# ClockGenerator.net
KiCad netlist of a schematic drawn in Altium Designer
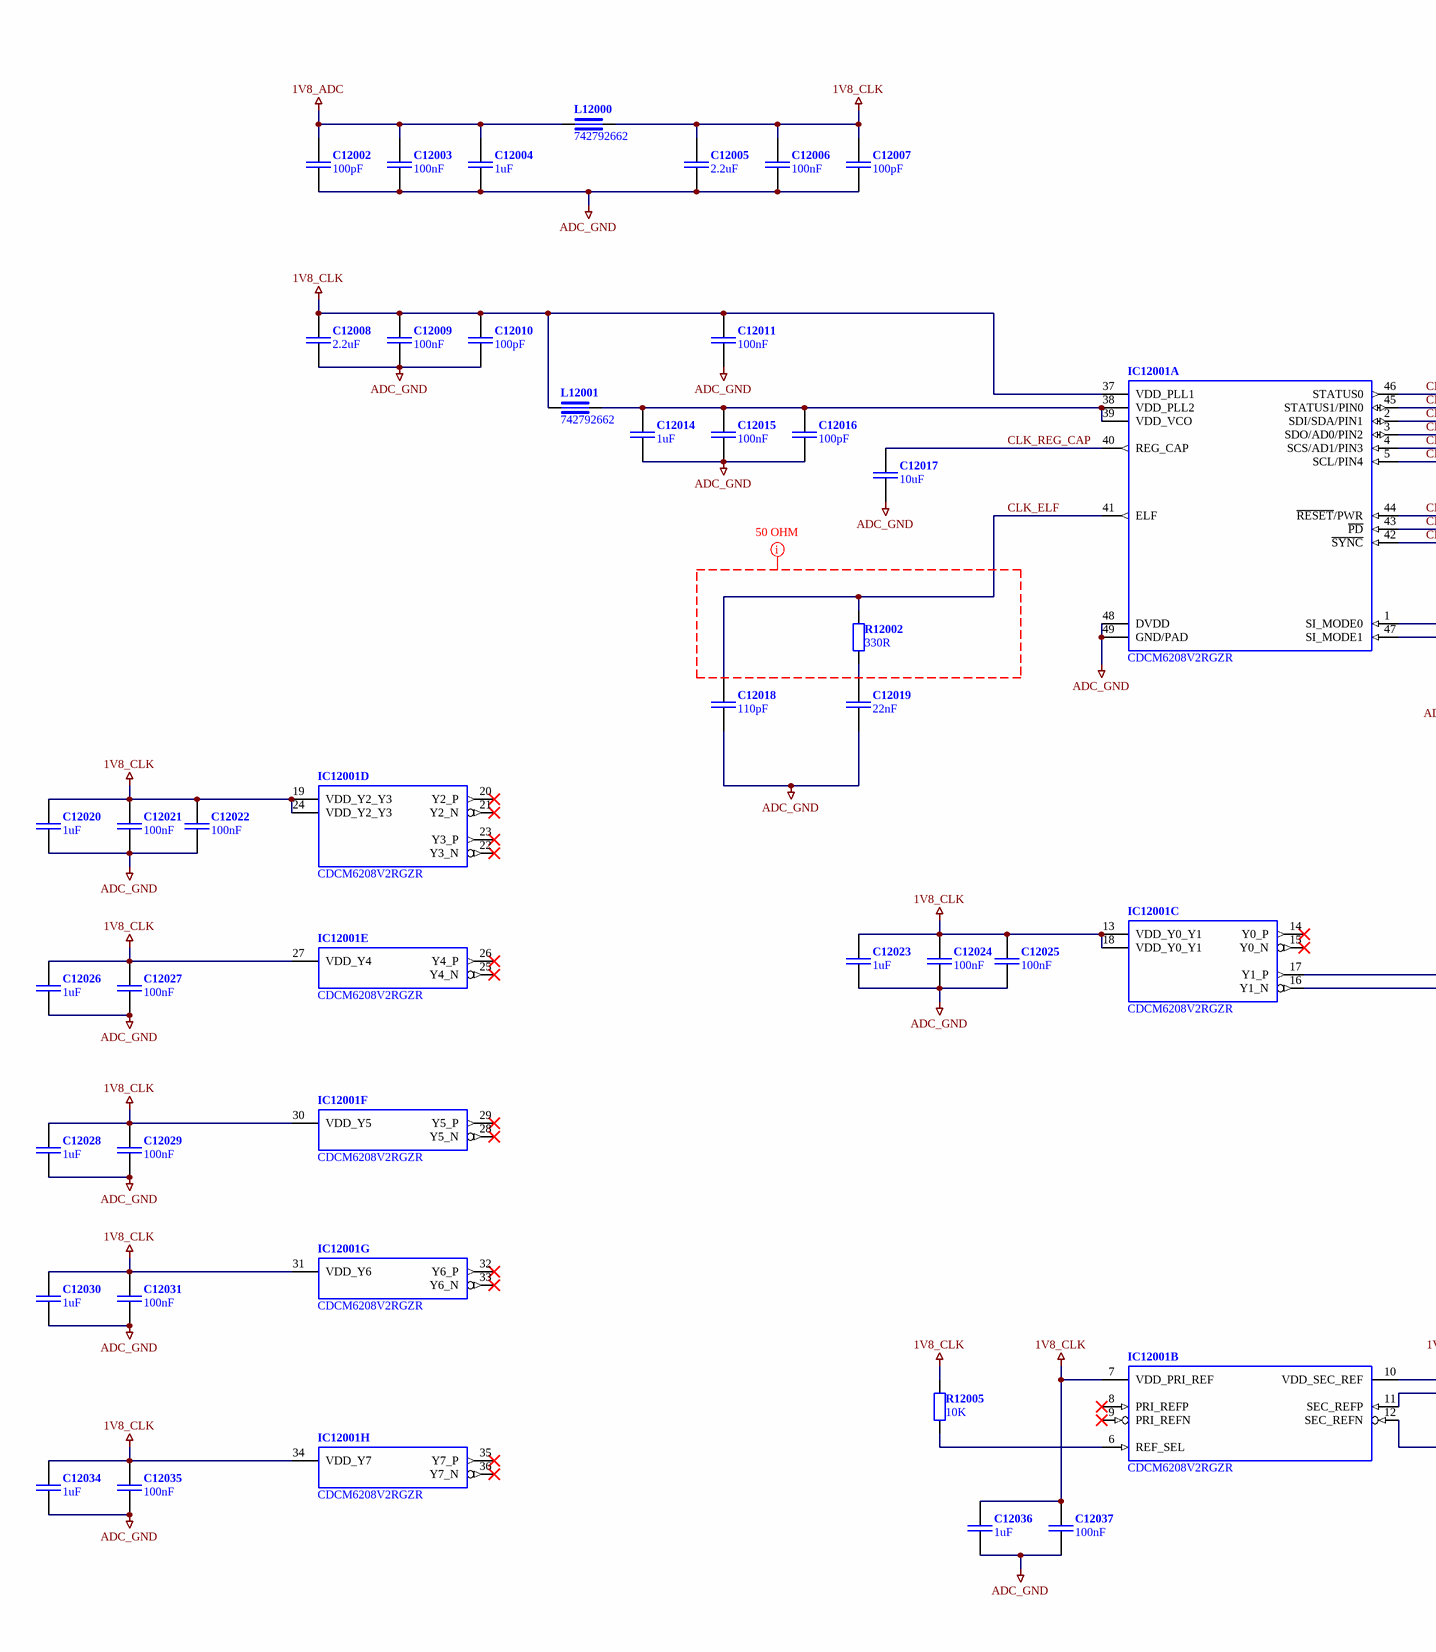
[diagram p0: ClockGenerator.SchDoc, left]
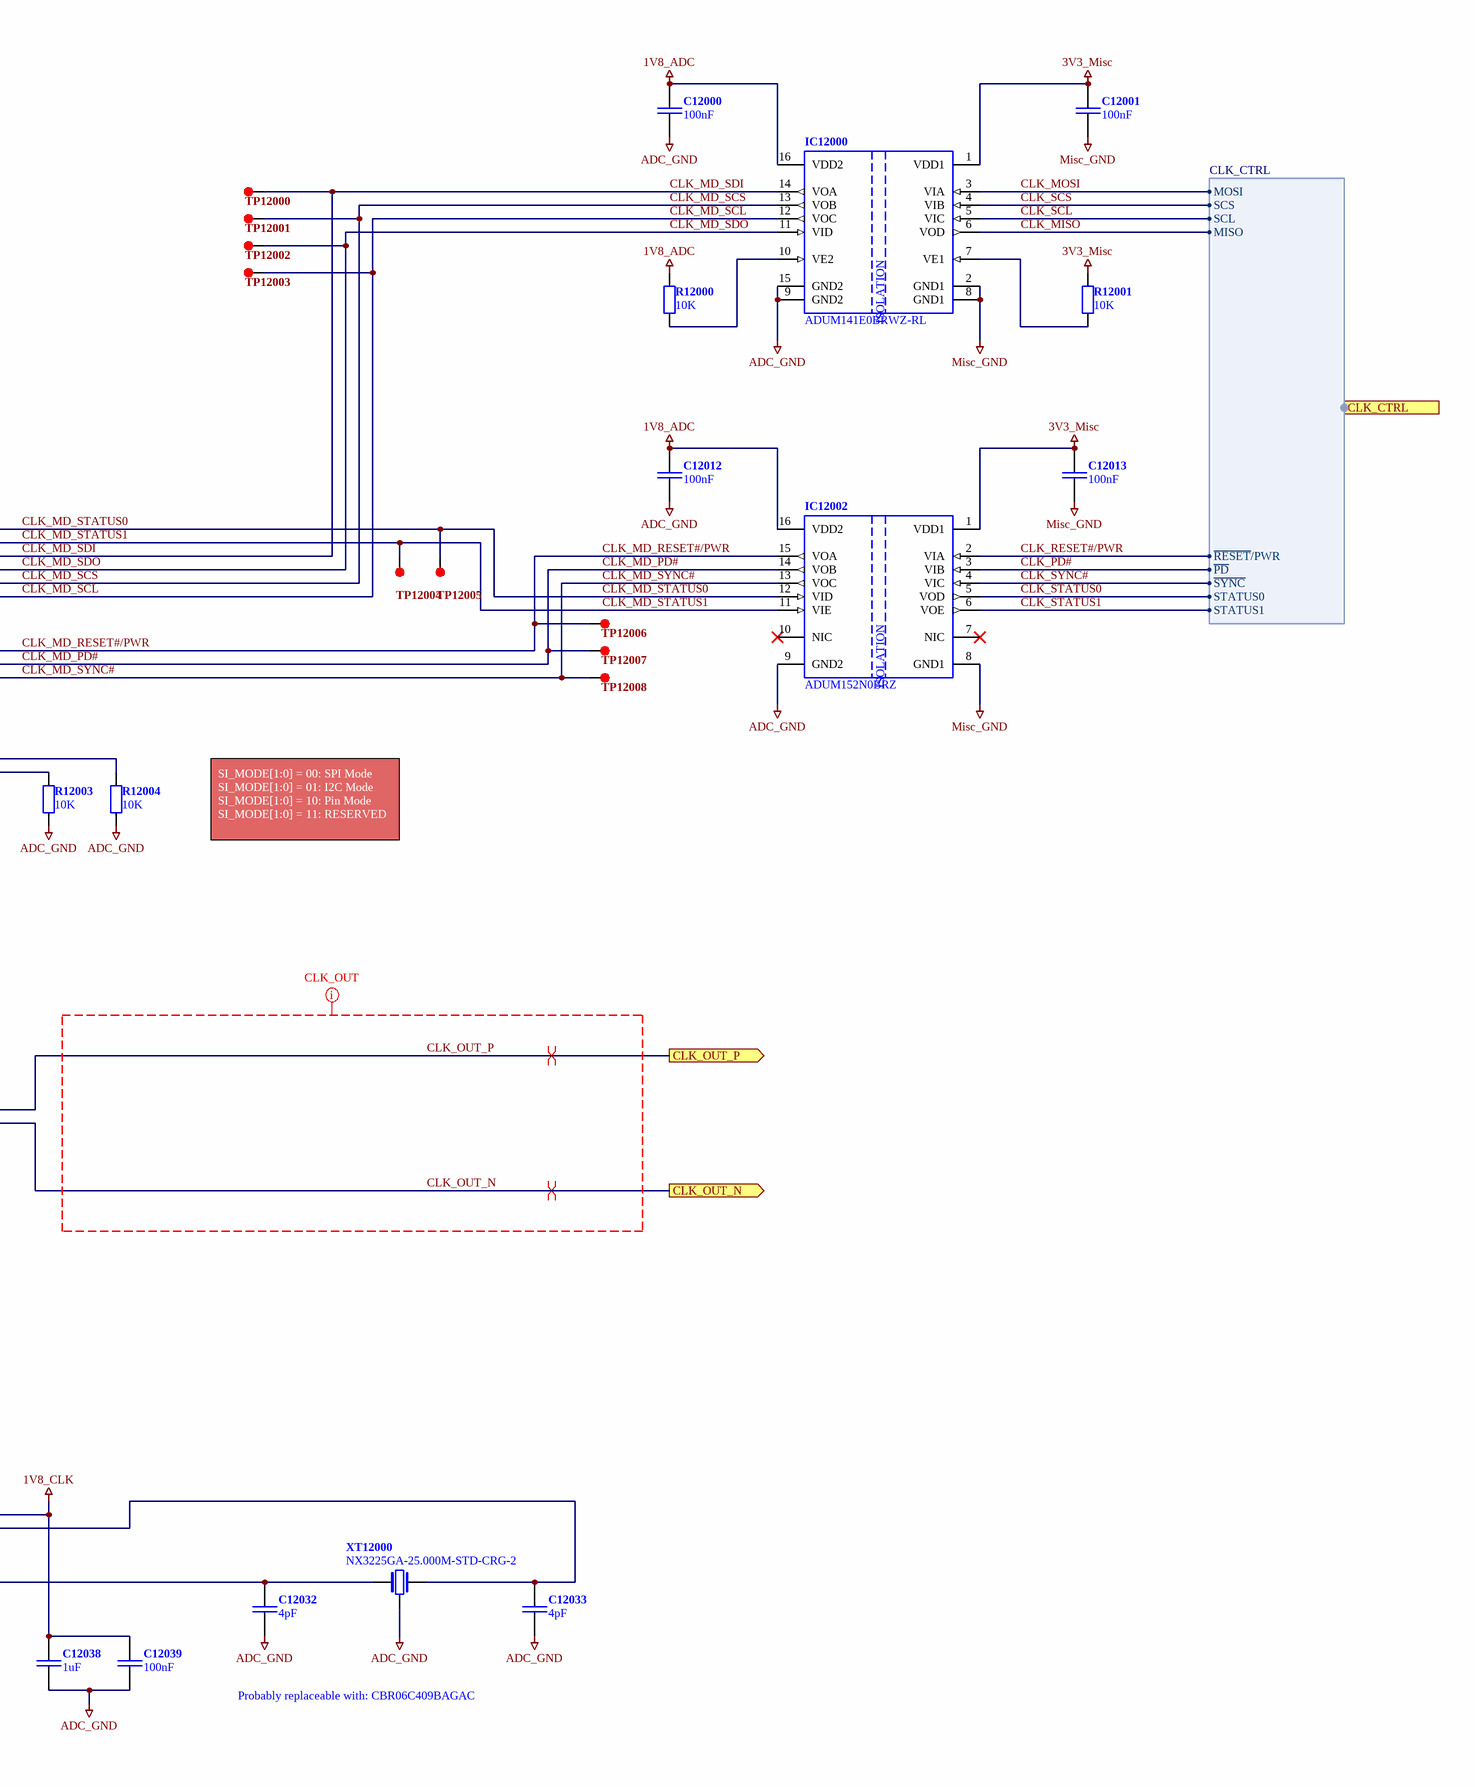
[diagram p1: ClockGenerator.SchDoc, right]

(export (version "E")
  (design (tool "Eeschema 10.0.6"))
  (components
    (comp (ref "C12000")
      (value "100nF")
      (footprint "PrometheusLib:C_0603_N [CAPC1608N IPC]")
      (libsource (lib "PrometheusLib") (part "C_GENERIC"))
    )
    (comp (ref "C12001")
      (value "100nF")
      (footprint "PrometheusLib:C_0603_N [CAPC1608N IPC]")
      (libsource (lib "PrometheusLib") (part "C_GENERIC"))
    )
    (comp (ref "C12002")
      (value "100pF")
      (footprint "PrometheusLib:C_0402_N [CAPC1005N IPC]")
      (libsource (lib "PrometheusLib") (part "C_GENERIC"))
    )
    (comp (ref "C12003")
      (value "100nF")
      (footprint "PrometheusLib:C_0603_N [CAPC1608N IPC]")
      (libsource (lib "PrometheusLib") (part "C_GENERIC"))
    )
    (comp (ref "C12004")
      (value "1uF")
      (footprint "PrometheusLib:C_0805_N [CAPC2013N IPC]")
      (libsource (lib "PrometheusLib") (part "C_GENERIC"))
    )
    (comp (ref "C12005")
      (value "2.2uF")
      (footprint "PrometheusLib:C_0805_N [CAPC2013N IPC]")
      (libsource (lib "PrometheusLib") (part "C_GENERIC"))
    )
    (comp (ref "C12006")
      (value "100nF")
      (footprint "PrometheusLib:C_0603_N [CAPC1608N IPC]")
      (libsource (lib "PrometheusLib") (part "C_GENERIC"))
    )
    (comp (ref "C12007")
      (value "100pF")
      (footprint "PrometheusLib:C_0402_N [CAPC1005N IPC]")
      (libsource (lib "PrometheusLib") (part "C_GENERIC"))
    )
    (comp (ref "C12008")
      (value "2.2uF")
      (footprint "PrometheusLib:C_0805_N [CAPC2013N IPC]")
      (libsource (lib "PrometheusLib") (part "C_GENERIC"))
    )
    (comp (ref "C12009")
      (value "100nF")
      (footprint "PrometheusLib:C_0603_N [CAPC1608N IPC]")
      (libsource (lib "PrometheusLib") (part "C_GENERIC"))
    )
    (comp (ref "C12010")
      (value "100pF")
      (footprint "PrometheusLib:C_0402_N [CAPC1005N IPC]")
      (libsource (lib "PrometheusLib") (part "C_GENERIC"))
    )
    (comp (ref "C12011")
      (value "100nF")
      (footprint "PrometheusLib:C_0603_N [CAPC1608N IPC]")
      (libsource (lib "PrometheusLib") (part "C_GENERIC"))
    )
    (comp (ref "C12012")
      (value "100nF")
      (footprint "PrometheusLib:C_0603_N [CAPC1608N IPC]")
      (libsource (lib "PrometheusLib") (part "C_GENERIC"))
    )
    (comp (ref "C12013")
      (value "100nF")
      (footprint "PrometheusLib:C_0603_N [CAPC1608N IPC]")
      (libsource (lib "PrometheusLib") (part "C_GENERIC"))
    )
    (comp (ref "C12014")
      (value "1uF")
      (footprint "PrometheusLib:C_0805_N [CAPC2013N IPC]")
      (libsource (lib "PrometheusLib") (part "C_GENERIC"))
    )
    (comp (ref "C12015")
      (value "100nF")
      (footprint "PrometheusLib:C_0603_N [CAPC1608N IPC]")
      (libsource (lib "PrometheusLib") (part "C_GENERIC"))
    )
    (comp (ref "C12016")
      (value "100pF")
      (footprint "PrometheusLib:C_0402_N [CAPC1005N IPC]")
      (libsource (lib "PrometheusLib") (part "C_GENERIC"))
    )
    (comp (ref "C12017")
      (value "10uF")
      (footprint "PrometheusLib:C_0805_N [CAPC2013N IPC]")
      (fields (field (name "PROMETHEUS_MANPARTNO") "GRM188R60J106KE47D"))
      (libsource (lib "PrometheusLib") (part "C_GENERIC"))
    )
    (comp (ref "C12018")
      (value "110pF")
      (footprint "PrometheusLib:C_0603_N [CAPC1608N IPC]")
      (libsource (lib "PrometheusLib") (part "C_GENERIC"))
    )
    (comp (ref "C12019")
      (value "22nF")
      (footprint "PrometheusLib:C_0603_N [CAPC1608N IPC]")
      (libsource (lib "PrometheusLib") (part "C_GENERIC"))
    )
    (comp (ref "C12020")
      (value "1uF")
      (footprint "PrometheusLib:C_0805_N [CAPC2013N IPC]")
      (libsource (lib "PrometheusLib") (part "C_GENERIC"))
    )
    (comp (ref "C12021")
      (value "100nF")
      (footprint "PrometheusLib:C_0603_N [CAPC1608N IPC]")
      (libsource (lib "PrometheusLib") (part "C_GENERIC"))
    )
    (comp (ref "C12022")
      (value "100nF")
      (footprint "PrometheusLib:C_0603_N [CAPC1608N IPC]")
      (libsource (lib "PrometheusLib") (part "C_GENERIC"))
    )
    (comp (ref "C12023")
      (value "1uF")
      (footprint "PrometheusLib:C_0805_N [CAPC2013N IPC]")
      (libsource (lib "PrometheusLib") (part "C_GENERIC"))
    )
    (comp (ref "C12024")
      (value "100nF")
      (footprint "PrometheusLib:C_0603_N [CAPC1608N IPC]")
      (libsource (lib "PrometheusLib") (part "C_GENERIC"))
    )
    (comp (ref "C12025")
      (value "100nF")
      (footprint "PrometheusLib:C_0603_N [CAPC1608N IPC]")
      (libsource (lib "PrometheusLib") (part "C_GENERIC"))
    )
    (comp (ref "C12026")
      (value "1uF")
      (footprint "PrometheusLib:C_0805_N [CAPC2013N IPC]")
      (libsource (lib "PrometheusLib") (part "C_GENERIC"))
    )
    (comp (ref "C12027")
      (value "100nF")
      (footprint "PrometheusLib:C_0603_N [CAPC1608N IPC]")
      (libsource (lib "PrometheusLib") (part "C_GENERIC"))
    )
    (comp (ref "C12028")
      (value "1uF")
      (footprint "PrometheusLib:C_0805_N [CAPC2013N IPC]")
      (libsource (lib "PrometheusLib") (part "C_GENERIC"))
    )
    (comp (ref "C12029")
      (value "100nF")
      (footprint "PrometheusLib:C_0603_N [CAPC1608N IPC]")
      (libsource (lib "PrometheusLib") (part "C_GENERIC"))
    )
    (comp (ref "C12030")
      (value "1uF")
      (footprint "PrometheusLib:C_0805_N [CAPC2013N IPC]")
      (libsource (lib "PrometheusLib") (part "C_GENERIC"))
    )
    (comp (ref "C12031")
      (value "100nF")
      (footprint "PrometheusLib:C_0603_N [CAPC1608N IPC]")
      (libsource (lib "PrometheusLib") (part "C_GENERIC"))
    )
    (comp (ref "C12032")
      (value "4pF")
      (footprint "PrometheusLib:C_0603_N [CAPC1608N IPC]")
      (description "+- 0.05 pF")
      (fields (field (name "PROMETHEUS_MANPARTNO") "CBR06C409A1GAC"))
      (libsource (lib "PrometheusLib") (part "C_GENERIC"))
    )
    (comp (ref "C12033")
      (value "4pF")
      (footprint "PrometheusLib:C_0603_N [CAPC1608N IPC]")
      (description "+- 0.05 pF")
      (fields (field (name "PROMETHEUS_MANPARTNO") "CBR06C409A1GAC"))
      (libsource (lib "PrometheusLib") (part "C_GENERIC"))
    )
    (comp (ref "C12034")
      (value "1uF")
      (footprint "PrometheusLib:C_0805_N [CAPC2013N IPC]")
      (libsource (lib "PrometheusLib") (part "C_GENERIC"))
    )
    (comp (ref "C12035")
      (value "100nF")
      (footprint "PrometheusLib:C_0603_N [CAPC1608N IPC]")
      (libsource (lib "PrometheusLib") (part "C_GENERIC"))
    )
    (comp (ref "C12036")
      (value "1uF")
      (footprint "PrometheusLib:C_0805_N [CAPC2013N IPC]")
      (libsource (lib "PrometheusLib") (part "C_GENERIC"))
    )
    (comp (ref "C12037")
      (value "100nF")
      (footprint "PrometheusLib:C_0603_N [CAPC1608N IPC]")
      (libsource (lib "PrometheusLib") (part "C_GENERIC"))
    )
    (comp (ref "C12038")
      (value "1uF")
      (footprint "PrometheusLib:C_0805_N [CAPC2013N IPC]")
      (libsource (lib "PrometheusLib") (part "C_GENERIC"))
    )
    (comp (ref "C12039")
      (value "100nF")
      (footprint "PrometheusLib:C_0603_N [CAPC1608N IPC]")
      (libsource (lib "PrometheusLib") (part "C_GENERIC"))
    )
    (comp (ref "IC12000")
      (value "ADUM141E0BRWZ-RL")
      (footprint "SOIC127P1030X265-16N IPC")
      (description "3/1 digital isolator\r\n1.8 V to 5 V Level translation")
      (libsource (lib "PrometheusLib") (part "IC_ADUM141E0BRWZ-RL"))
    )
    (comp (ref "IC12001")
      (value "CDCM6208V2RGZR")
      (footprint "QFN50P700X700X100_HS-49N IPC")
      (description "2:8 Clock Generator, Jitter Cleaner with fractional dividers")
      (libsource (lib "PrometheusLib") (part "IC_CDCM6208V2"))
    )
    (comp (ref "IC12002")
      (value "ADUM152N0BRZ")
      (footprint "SOIC127P600X175-16N IPC")
      (description "3/2 digital isolator\r\n1.8 V to 5 V Level translation")
      (libsource (lib "PrometheusLib") (part "IC_ADUM152N0BRZ"))
    )
    (comp (ref "L12000")
      (value "742792662")
      (footprint "PrometheusLib:L_0603_N [INDC1608N IPC]")
      (libsource (lib "PrometheusLib") (part "FB_GENERIC"))
    )
    (comp (ref "L12001")
      (value "742792662")
      (footprint "PrometheusLib:L_0603_N [INDC1608N IPC]")
      (libsource (lib "PrometheusLib") (part "FB_GENERIC"))
    )
    (comp (ref "R12000")
      (value "10K")
      (footprint "PrometheusLib:R_0603_N [RESC1608N IPC]")
      (libsource (lib "PrometheusLib") (part "R_GENERIC_DIN"))
    )
    (comp (ref "R12001")
      (value "10K")
      (footprint "PrometheusLib:R_0603_N [RESC1608N IPC]")
      (libsource (lib "") (part "R_GENERIC_DIN_1"))
    )
    (comp (ref "R12002")
      (value "330R")
      (footprint "PrometheusLib:R_0603_N [RESC1608N IPC]")
      (fields (field (name "PROMETHEUS_MANPARTNO") "ERJ-3EKF3300V"))
      (libsource (lib "PrometheusLib") (part "R_GENERIC_DIN"))
    )
    (comp (ref "R12003")
      (value "10K")
      (footprint "PrometheusLib:R_0603_N [RESC1608N IPC]")
      (libsource (lib "PrometheusLib") (part "R_GENERIC_DIN"))
    )
    (comp (ref "R12004")
      (value "10K")
      (footprint "PrometheusLib:R_0603_N [RESC1608N IPC]")
      (libsource (lib "PrometheusLib") (part "R_GENERIC_DIN"))
    )
    (comp (ref "R12005")
      (value "10K")
      (footprint "PrometheusLib:R_0603_N [RESC1608N IPC]")
      (libsource (lib "PrometheusLib") (part "R_GENERIC_DIN"))
    )
    (comp (ref "TP12000")
      (value "TP_GENERIC")
      (footprint "PrometheusLib:TP_0.8_P100T")
      (description "Needle Test Point")
      (libsource (lib "PrometheusLib") (part "TP_GENERIC"))
    )
    (comp (ref "TP12001")
      (value "TP_GENERIC")
      (footprint "PrometheusLib:TP_0.8_P100T")
      (description "Needle Test Point")
      (libsource (lib "PrometheusLib") (part "TP_GENERIC"))
    )
    (comp (ref "TP12002")
      (value "TP_GENERIC")
      (footprint "PrometheusLib:TP_0.8_P100T")
      (description "Needle Test Point")
      (libsource (lib "PrometheusLib") (part "TP_GENERIC"))
    )
    (comp (ref "TP12003")
      (value "TP_GENERIC")
      (footprint "PrometheusLib:TP_0.8_P100T")
      (description "Needle Test Point")
      (libsource (lib "PrometheusLib") (part "TP_GENERIC"))
    )
    (comp (ref "TP12004")
      (value "TP_GENERIC")
      (footprint "PrometheusLib:TP_0.8_P100T")
      (description "Needle Test Point")
      (libsource (lib "PrometheusLib") (part "TP_GENERIC"))
    )
    (comp (ref "TP12005")
      (value "TP_GENERIC")
      (footprint "PrometheusLib:TP_0.8_P100T")
      (description "Needle Test Point")
      (libsource (lib "PrometheusLib") (part "TP_GENERIC"))
    )
    (comp (ref "TP12006")
      (value "TP_GENERIC")
      (footprint "PrometheusLib:TP_0.8_P100T")
      (description "Needle Test Point")
      (libsource (lib "PrometheusLib") (part "TP_GENERIC"))
    )
    (comp (ref "TP12007")
      (value "TP_GENERIC")
      (footprint "PrometheusLib:TP_0.8_P100T")
      (description "Needle Test Point")
      (libsource (lib "PrometheusLib") (part "TP_GENERIC"))
    )
    (comp (ref "TP12008")
      (value "TP_GENERIC")
      (footprint "PrometheusLib:TP_0.8_P100T")
      (description "Needle Test Point")
      (libsource (lib "PrometheusLib") (part "TP_GENERIC"))
    )
    (comp (ref "XT12000")
      (value "NX3225GA-25.000M-STD-CRG-2")
      (footprint "PrometheusLib:XT_SMD_320x250_H100_4PIN")
      (description "25 MHz\r\n8 pF")
      (libsource (lib "PrometheusLib") (part "XT_NX3225GA-25.000M-STD-CRG-2"))
    )
  )
  (nets
    (net (code "2") (name "/CLK_ELF") (class "Default")
      (node (ref "C12018") (pin "2") (pintype "passive"))
      (node (ref "IC12001") (pin "41") (pinfunction "ELF_41") (pintype "output"))
      (node (ref "R12002") (pin "2") (pinfunction "2_2") (pintype "passive"))
    )
    (net (code "3") (name "/CLK_MD_PD#") (class "Default")
      (node (ref "IC12001") (pin "43") (pinfunction "~{PD}_43") (pintype "input"))
      (node (ref "IC12002") (pin "14") (pinfunction "VOB_14") (pintype "output"))
      (node (ref "TP12007") (pin "1") (pinfunction "1_1") (pintype "passive"))
    )
    (net (code "4") (name "/CLK_MD_RESET#{slash}PWR") (class "Default")
      (node (ref "IC12001") (pin "44") (pinfunction "~{RESET}/PWR_44") (pintype "input"))
      (node (ref "IC12002") (pin "15") (pinfunction "VOA_15") (pintype "output"))
      (node (ref "TP12006") (pin "1") (pinfunction "1_1") (pintype "passive"))
    )
    (net (code "5") (name "/CLK_MD_SCL") (class "Default")
      (node (ref "IC12000") (pin "12") (pinfunction "VOC_12") (pintype "output"))
      (node (ref "IC12001") (pin "5") (pinfunction "SCL/PIN4_5") (pintype "input"))
      (node (ref "TP12003") (pin "1") (pinfunction "1_1") (pintype "passive"))
    )
    (net (code "6") (name "/CLK_MD_SCS") (class "Default")
      (node (ref "IC12000") (pin "13") (pinfunction "VOB_13") (pintype "output"))
      (node (ref "IC12001") (pin "4") (pinfunction "SCS/AD1/PIN3_4") (pintype "input"))
      (node (ref "TP12001") (pin "1") (pinfunction "1_1") (pintype "passive"))
    )
    (net (code "7") (name "/CLK_MD_SDI") (class "Default")
      (node (ref "IC12000") (pin "14") (pinfunction "VOA_14") (pintype "output"))
      (node (ref "IC12001") (pin "2") (pinfunction "SDI/SDA/PIN1_2") (pintype "bidirectional"))
      (node (ref "TP12000") (pin "1") (pinfunction "1_1") (pintype "passive"))
    )
    (net (code "8") (name "/CLK_MD_SDO") (class "Default")
      (node (ref "IC12000") (pin "11") (pinfunction "VID_11") (pintype "input"))
      (node (ref "IC12001") (pin "3") (pinfunction "SDO/AD0/PIN2_3") (pintype "bidirectional"))
      (node (ref "TP12002") (pin "1") (pinfunction "1_1") (pintype "passive"))
    )
    (net (code "9") (name "/CLK_MD_STATUS0") (class "Default")
      (node (ref "IC12001") (pin "46") (pinfunction "STATUS0_46") (pintype "output"))
      (node (ref "IC12002") (pin "12") (pinfunction "VID_12") (pintype "input"))
      (node (ref "TP12005") (pin "1") (pinfunction "1_1") (pintype "passive"))
    )
    (net (code "10") (name "/CLK_MD_STATUS1") (class "Default")
      (node (ref "IC12001") (pin "45") (pinfunction "STATUS1/PIN0_45") (pintype "bidirectional"))
      (node (ref "IC12002") (pin "11") (pinfunction "VIE_11") (pintype "input"))
      (node (ref "TP12004") (pin "1") (pinfunction "1_1") (pintype "passive"))
    )
    (net (code "11") (name "/CLK_MD_SYNC#") (class "Default")
      (node (ref "IC12001") (pin "42") (pinfunction "~{SYNC}_42") (pintype "input"))
      (node (ref "IC12002") (pin "13") (pinfunction "VOC_13") (pintype "output"))
      (node (ref "TP12008") (pin "1") (pinfunction "1_1") (pintype "passive"))
    )
    (net (code "12") (name "/CLK_MISO") (class "Default")
      (node (ref "IC12000") (pin "6") (pinfunction "VOD_6") (pintype "output"))
    )
    (net (code "13") (name "/CLK_MOSI") (class "Default")
      (node (ref "IC12000") (pin "3") (pinfunction "VIA_3") (pintype "input"))
    )
    (net (code "14") (name "/CLK_OUT_N") (class "Default")
      (node (ref "IC12001") (pin "16") (pinfunction "Y1_N_16") (pintype "output"))
    )
    (net (code "15") (name "/CLK_OUT_P") (class "Default")
      (node (ref "IC12001") (pin "17") (pinfunction "Y1_P_17") (pintype "output"))
    )
    (net (code "16") (name "/CLK_PD#") (class "Default")
      (node (ref "IC12002") (pin "3") (pinfunction "VIB_3") (pintype "input"))
    )
    (net (code "17") (name "/CLK_REG_CAP") (class "Default")
      (node (ref "C12017") (pin "1") (pintype "passive"))
      (node (ref "IC12001") (pin "40") (pinfunction "REG_CAP_40") (pintype "output"))
    )
    (net (code "18") (name "/CLK_RESET#{slash}PWR") (class "Default")
      (node (ref "IC12002") (pin "2") (pinfunction "VIA_2") (pintype "input"))
    )
    (net (code "19") (name "/CLK_SCL") (class "Default")
      (node (ref "IC12000") (pin "5") (pinfunction "VIC_5") (pintype "input"))
    )
    (net (code "20") (name "/CLK_SCS") (class "Default")
      (node (ref "IC12000") (pin "4") (pinfunction "VIB_4") (pintype "input"))
    )
    (net (code "21") (name "/CLK_STATUS0") (class "Default")
      (node (ref "IC12002") (pin "5") (pinfunction "VOD_5") (pintype "output"))
    )
    (net (code "22") (name "/CLK_STATUS1") (class "Default")
      (node (ref "IC12002") (pin "6") (pinfunction "VOE_6") (pintype "output"))
    )
    (net (code "23") (name "/CLK_SYNC#") (class "Default")
      (node (ref "IC12002") (pin "4") (pinfunction "VIC_4") (pintype "input"))
    )
    (net (code "25") (name "1V8_ADC") (class "Default")
      (node (ref "C12000") (pin "1") (pintype "passive"))
      (node (ref "C12002") (pin "1") (pintype "passive"))
      (node (ref "C12003") (pin "1") (pintype "passive"))
      (node (ref "C12004") (pin "1") (pintype "passive"))
      (node (ref "C12012") (pin "1") (pintype "passive"))
      (node (ref "IC12000") (pin "16") (pinfunction "VDD2_16") (pintype "passive"))
      (node (ref "IC12002") (pin "16") (pinfunction "VDD2_16") (pintype "passive"))
      (node (ref "L12000") (pin "2") (pintype "passive"))
      (node (ref "R12000") (pin "2") (pinfunction "2_2") (pintype "passive"))
    )
    (net (code "26") (name "1V8_CLK") (class "Default")
      (node (ref "C12005") (pin "1") (pintype "passive"))
      (node (ref "C12006") (pin "1") (pintype "passive"))
      (node (ref "C12007") (pin "1") (pintype "passive"))
      (node (ref "C12008") (pin "1") (pintype "passive"))
      (node (ref "C12009") (pin "1") (pintype "passive"))
      (node (ref "C12010") (pin "1") (pintype "passive"))
      (node (ref "C12011") (pin "1") (pintype "passive"))
      (node (ref "C12020") (pin "1") (pintype "passive"))
      (node (ref "C12021") (pin "1") (pintype "passive"))
      (node (ref "C12022") (pin "1") (pintype "passive"))
      (node (ref "C12023") (pin "1") (pintype "passive"))
      (node (ref "C12024") (pin "1") (pintype "passive"))
      (node (ref "C12025") (pin "1") (pintype "passive"))
      (node (ref "C12026") (pin "1") (pintype "passive"))
      (node (ref "C12027") (pin "1") (pintype "passive"))
      (node (ref "C12028") (pin "1") (pintype "passive"))
      (node (ref "C12029") (pin "1") (pintype "passive"))
      (node (ref "C12030") (pin "1") (pintype "passive"))
      (node (ref "C12031") (pin "1") (pintype "passive"))
      (node (ref "C12034") (pin "1") (pintype "passive"))
      (node (ref "C12035") (pin "1") (pintype "passive"))
      (node (ref "C12036") (pin "1") (pintype "passive"))
      (node (ref "C12037") (pin "1") (pintype "passive"))
      (node (ref "C12038") (pin "1") (pintype "passive"))
      (node (ref "C12039") (pin "1") (pintype "passive"))
      (node (ref "IC12001") (pin "10") (pinfunction "VDD_SEC_REF_10") (pintype "passive"))
      (node (ref "IC12001") (pin "13") (pinfunction "VDD_Y0_Y1_13") (pintype "passive"))
      (node (ref "IC12001") (pin "18") (pinfunction "VDD_Y0_Y1_18") (pintype "passive"))
      (node (ref "IC12001") (pin "19") (pinfunction "VDD_Y2_Y3_19") (pintype "passive"))
      (node (ref "IC12001") (pin "24") (pinfunction "VDD_Y2_Y3_24") (pintype "passive"))
      (node (ref "IC12001") (pin "27") (pinfunction "VDD_Y4_27") (pintype "passive"))
      (node (ref "IC12001") (pin "30") (pinfunction "VDD_Y5_30") (pintype "passive"))
      (node (ref "IC12001") (pin "31") (pinfunction "VDD_Y6_31") (pintype "passive"))
      (node (ref "IC12001") (pin "34") (pinfunction "VDD_Y7_34") (pintype "passive"))
      (node (ref "IC12001") (pin "37") (pinfunction "VDD_PLL1_37") (pintype "passive"))
      (node (ref "IC12001") (pin "7") (pinfunction "VDD_PRI_REF_7") (pintype "passive"))
      (node (ref "L12000") (pin "1") (pintype "passive"))
      (node (ref "L12001") (pin "2") (pintype "passive"))
      (node (ref "R12005") (pin "2") (pinfunction "2_2") (pintype "passive"))
    )
    (net (code "27") (name "3V3_Misc") (class "Default")
      (node (ref "C12001") (pin "1") (pintype "passive"))
      (node (ref "C12013") (pin "1") (pintype "passive"))
      (node (ref "IC12000") (pin "1") (pinfunction "VDD1_1") (pintype "passive"))
      (node (ref "IC12002") (pin "1") (pinfunction "VDD1_1") (pintype "passive"))
      (node (ref "R12001") (pin "2") (pinfunction "2_2") (pintype "passive"))
    )
    (net (code "28") (name "ADC_GND") (class "Default")
      (node (ref "C12000") (pin "2") (pintype "passive"))
      (node (ref "C12002") (pin "2") (pintype "passive"))
      (node (ref "C12003") (pin "2") (pintype "passive"))
      (node (ref "C12004") (pin "2") (pintype "passive"))
      (node (ref "C12005") (pin "2") (pintype "passive"))
      (node (ref "C12006") (pin "2") (pintype "passive"))
      (node (ref "C12007") (pin "2") (pintype "passive"))
      (node (ref "C12008") (pin "2") (pintype "passive"))
      (node (ref "C12009") (pin "2") (pintype "passive"))
      (node (ref "C12010") (pin "2") (pintype "passive"))
      (node (ref "C12011") (pin "2") (pintype "passive"))
      (node (ref "C12012") (pin "2") (pintype "passive"))
      (node (ref "C12014") (pin "2") (pintype "passive"))
      (node (ref "C12015") (pin "2") (pintype "passive"))
      (node (ref "C12016") (pin "2") (pintype "passive"))
      (node (ref "C12017") (pin "2") (pintype "passive"))
      (node (ref "C12018") (pin "1") (pintype "passive"))
      (node (ref "C12019") (pin "1") (pintype "passive"))
      (node (ref "C12020") (pin "2") (pintype "passive"))
      (node (ref "C12021") (pin "2") (pintype "passive"))
      (node (ref "C12022") (pin "2") (pintype "passive"))
      (node (ref "C12023") (pin "2") (pintype "passive"))
      (node (ref "C12024") (pin "2") (pintype "passive"))
      (node (ref "C12025") (pin "2") (pintype "passive"))
      (node (ref "C12026") (pin "2") (pintype "passive"))
      (node (ref "C12027") (pin "2") (pintype "passive"))
      (node (ref "C12028") (pin "2") (pintype "passive"))
      (node (ref "C12029") (pin "2") (pintype "passive"))
      (node (ref "C12030") (pin "2") (pintype "passive"))
      (node (ref "C12031") (pin "2") (pintype "passive"))
      (node (ref "C12032") (pin "2") (pintype "passive"))
      (node (ref "C12033") (pin "2") (pintype "passive"))
      (node (ref "C12034") (pin "2") (pintype "passive"))
      (node (ref "C12035") (pin "2") (pintype "passive"))
      (node (ref "C12036") (pin "2") (pintype "passive"))
      (node (ref "C12037") (pin "2") (pintype "passive"))
      (node (ref "C12038") (pin "2") (pintype "passive"))
      (node (ref "C12039") (pin "2") (pintype "passive"))
      (node (ref "IC12000") (pin "15") (pinfunction "GND2_15") (pintype "passive"))
      (node (ref "IC12000") (pin "9") (pinfunction "GND2_9") (pintype "passive"))
      (node (ref "IC12001") (pin "48") (pinfunction "DVDD_48") (pintype "passive"))
      (node (ref "IC12001") (pin "49") (pinfunction "GND/PAD_49") (pintype "passive"))
      (node (ref "IC12002") (pin "9") (pinfunction "GND2_9") (pintype "passive"))
      (node (ref "R12003") (pin "1") (pinfunction "1_1") (pintype "passive"))
      (node (ref "R12004") (pin "1") (pinfunction "1_1") (pintype "passive"))
      (node (ref "XT12000") (pin "SH") (pinfunction "SH_SH") (pintype "passive"))
    )
    (net (code "29") (name "Misc_GND") (class "Default")
      (node (ref "C12001") (pin "2") (pintype "passive"))
      (node (ref "C12013") (pin "2") (pintype "passive"))
      (node (ref "IC12000") (pin "2") (pinfunction "GND1_2") (pintype "passive"))
      (node (ref "IC12000") (pin "8") (pinfunction "GND1_8") (pintype "passive"))
      (node (ref "IC12002") (pin "8") (pinfunction "GND1_8") (pintype "passive"))
    )
    (net (code "30") (name "Net-(C12019-Pad2)") (class "Default")
      (node (ref "C12019") (pin "2") (pintype "passive"))
      (node (ref "R12002") (pin "1") (pinfunction "1_1") (pintype "passive"))
    )
    (net (code "31") (name "Net-(IC12000-VE1)") (class "Default")
      (node (ref "IC12000") (pin "7") (pinfunction "VE1_7") (pintype "input"))
      (node (ref "R12001") (pin "1") (pinfunction "1_1") (pintype "passive"))
    )
    (net (code "32") (name "Net-(IC12000-VE2)") (class "Default")
      (node (ref "IC12000") (pin "10") (pinfunction "VE2_10") (pintype "input"))
      (node (ref "R12000") (pin "1") (pinfunction "1_1") (pintype "passive"))
    )
    (net (code "33") (name "Net-(IC12001A-SI_MODE0)") (class "Default")
      (node (ref "IC12001") (pin "1") (pinfunction "SI_MODE0_1") (pintype "input"))
      (node (ref "R12004") (pin "2") (pinfunction "2_2") (pintype "passive"))
    )
    (net (code "34") (name "Net-(IC12001A-SI_MODE1)") (class "Default")
      (node (ref "IC12001") (pin "47") (pinfunction "SI_MODE1_47") (pintype "input"))
      (node (ref "R12003") (pin "2") (pinfunction "2_2") (pintype "passive"))
    )
    (net (code "35") (name "Net-(IC12001A-VDD_PLL2)") (class "Default")
      (node (ref "C12014") (pin "1") (pintype "passive"))
      (node (ref "C12015") (pin "1") (pintype "passive"))
      (node (ref "C12016") (pin "1") (pintype "passive"))
      (node (ref "IC12001") (pin "38") (pinfunction "VDD_PLL2_38") (pintype "passive"))
      (node (ref "IC12001") (pin "39") (pinfunction "VDD_VCO_39") (pintype "passive"))
      (node (ref "L12001") (pin "1") (pintype "passive"))
    )
    (net (code "36") (name "Net-(IC12001B-REF_SEL)") (class "Default")
      (node (ref "IC12001") (pin "6") (pinfunction "REF_SEL_6") (pintype "input"))
      (node (ref "R12005") (pin "1") (pinfunction "1_1") (pintype "passive"))
    )
    (net (code "37") (name "Net-(IC12001B-SEC_REFN)") (class "Default")
      (node (ref "C12032") (pin "1") (pintype "passive"))
      (node (ref "IC12001") (pin "12") (pinfunction "SEC_REFN_12") (pintype "input"))
      (node (ref "XT12000") (pin "3") (pinfunction "3_3") (pintype "passive"))
    )
    (net (code "38") (name "Net-(IC12001B-SEC_REFP)") (class "Default")
      (node (ref "C12033") (pin "1") (pintype "passive"))
      (node (ref "IC12001") (pin "11") (pinfunction "SEC_REFP_11") (pintype "input"))
      (node (ref "XT12000") (pin "1") (pinfunction "1_1") (pintype "passive"))
    )
    (net (code "39") (name "unconnected-(IC12001B-PRI_REFN-Pad9)") (class "Default")
      (node (ref "IC12001") (pin "9") (pinfunction "PRI_REFN_9") (pintype "input+no_connect"))
    )
    (net (code "40") (name "unconnected-(IC12001B-PRI_REFP-Pad8)") (class "Default")
      (node (ref "IC12001") (pin "8") (pinfunction "PRI_REFP_8") (pintype "input+no_connect"))
    )
    (net (code "41") (name "unconnected-(IC12001C-Y0_N-Pad15)") (class "Default")
      (node (ref "IC12001") (pin "15") (pinfunction "Y0_N_15") (pintype "output+no_connect"))
    )
    (net (code "42") (name "unconnected-(IC12001C-Y0_P-Pad14)") (class "Default")
      (node (ref "IC12001") (pin "14") (pinfunction "Y0_P_14") (pintype "output+no_connect"))
    )
    (net (code "43") (name "unconnected-(IC12001D-Y2_N-Pad21)") (class "Default")
      (node (ref "IC12001") (pin "21") (pinfunction "Y2_N_21") (pintype "output+no_connect"))
    )
    (net (code "44") (name "unconnected-(IC12001D-Y2_P-Pad20)") (class "Default")
      (node (ref "IC12001") (pin "20") (pinfunction "Y2_P_20") (pintype "output+no_connect"))
    )
    (net (code "45") (name "unconnected-(IC12001D-Y3_N-Pad22)") (class "Default")
      (node (ref "IC12001") (pin "22") (pinfunction "Y3_N_22") (pintype "output+no_connect"))
    )
    (net (code "46") (name "unconnected-(IC12001D-Y3_P-Pad23)") (class "Default")
      (node (ref "IC12001") (pin "23") (pinfunction "Y3_P_23") (pintype "output+no_connect"))
    )
    (net (code "47") (name "unconnected-(IC12001E-Y4_N-Pad25)") (class "Default")
      (node (ref "IC12001") (pin "25") (pinfunction "Y4_N_25") (pintype "output+no_connect"))
    )
    (net (code "48") (name "unconnected-(IC12001E-Y4_P-Pad26)") (class "Default")
      (node (ref "IC12001") (pin "26") (pinfunction "Y4_P_26") (pintype "output+no_connect"))
    )
    (net (code "49") (name "unconnected-(IC12001F-Y5_N-Pad28)") (class "Default")
      (node (ref "IC12001") (pin "28") (pinfunction "Y5_N_28") (pintype "output+no_connect"))
    )
    (net (code "50") (name "unconnected-(IC12001F-Y5_P-Pad29)") (class "Default")
      (node (ref "IC12001") (pin "29") (pinfunction "Y5_P_29") (pintype "output+no_connect"))
    )
    (net (code "51") (name "unconnected-(IC12001G-Y6_N-Pad33)") (class "Default")
      (node (ref "IC12001") (pin "33") (pinfunction "Y6_N_33") (pintype "output+no_connect"))
    )
    (net (code "52") (name "unconnected-(IC12001G-Y6_P-Pad32)") (class "Default")
      (node (ref "IC12001") (pin "32") (pinfunction "Y6_P_32") (pintype "output+no_connect"))
    )
    (net (code "53") (name "unconnected-(IC12001H-Y7_N-Pad36)") (class "Default")
      (node (ref "IC12001") (pin "36") (pinfunction "Y7_N_36") (pintype "output+no_connect"))
    )
    (net (code "54") (name "unconnected-(IC12001H-Y7_P-Pad35)") (class "Default")
      (node (ref "IC12001") (pin "35") (pinfunction "Y7_P_35") (pintype "output+no_connect"))
    )
    (net (code "55") (name "unconnected-(IC12002-NIC-Pad7)") (class "Default")
      (node (ref "IC12002") (pin "7") (pinfunction "NIC_7") (pintype "passive+no_connect"))
    )
    (net (code "56") (name "unconnected-(IC12002-NIC-Pad10)") (class "Default")
      (node (ref "IC12002") (pin "10") (pinfunction "NIC_10") (pintype "passive+no_connect"))
    )
  )
)
